# MCU.net
KiCad netlist of a schematic drawn in Altium Designer
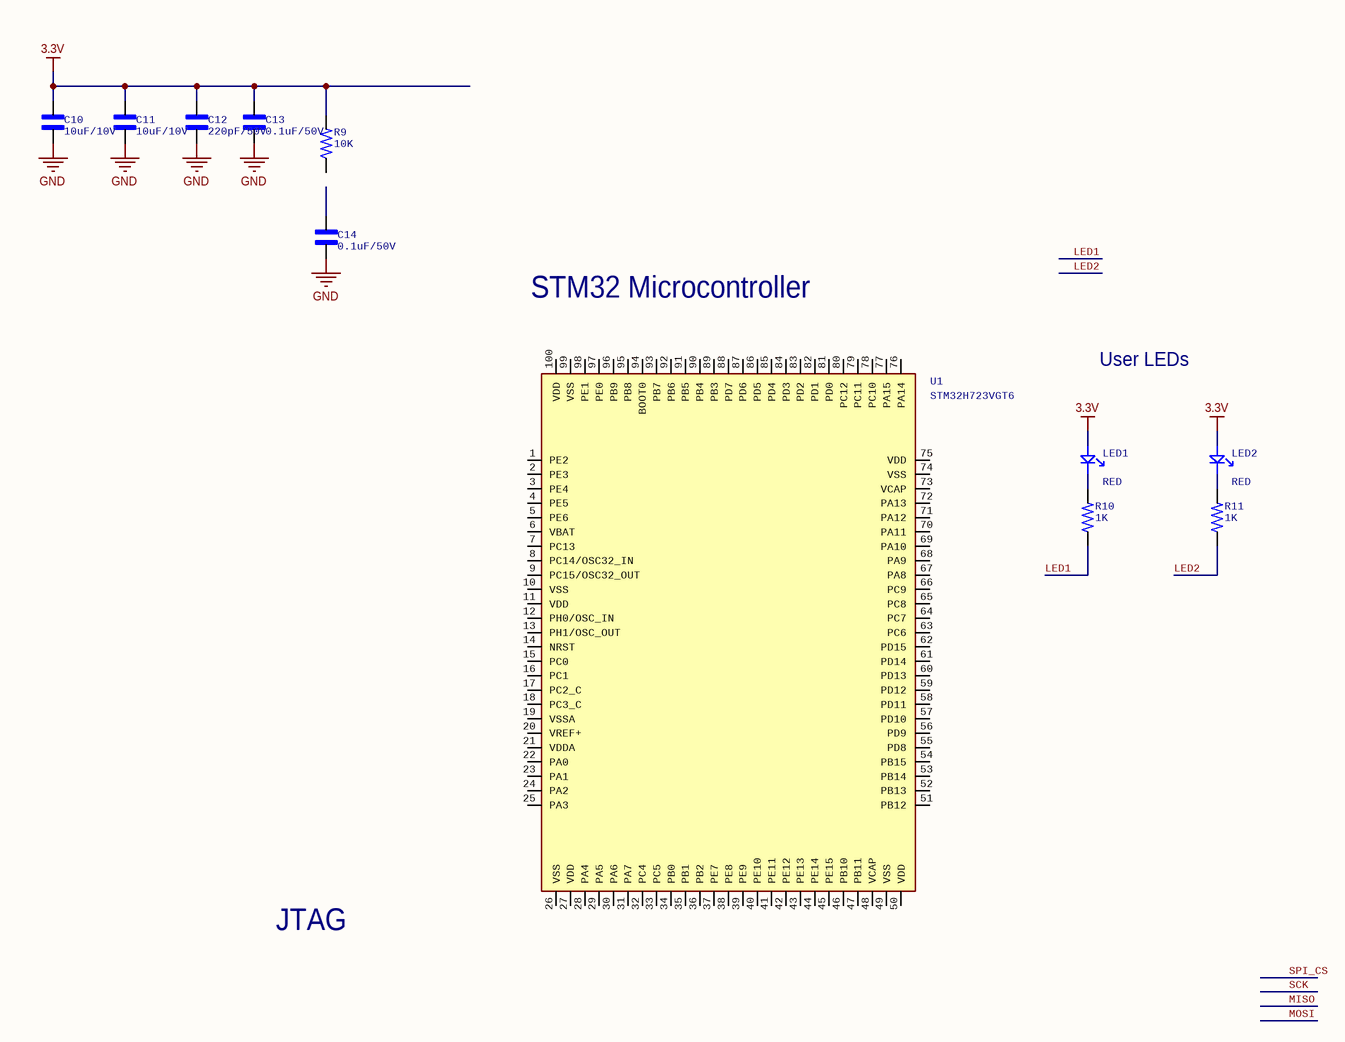
[diagram p0: MCU.SchDoc]

(export (version "E")
  (design (tool "Eeschema 10.0.6"))
  (components
    (comp (ref "C10")
      (value "10uF/10V")
      (footprint "C0603")
      (description "MLCC 10uF 10V X5R 20% 0603")
      (fields
        (field (name "MANUFACTURER") "KEMET")
        (field (name "MANUFACTURER PART NUMBER") "C0603C106M8PAC7867")
      )
      (libsource (lib "Capacitors") (part "C0603 10uF/10V"))
    )
    (comp (ref "C11")
      (value "10uF/10V")
      (footprint "C0603")
      (description "MLCC 10uF 10V X5R 20% 0603")
      (fields
        (field (name "MANUFACTURER") "KEMET")
        (field (name "MANUFACTURER PART NUMBER") "C0603C106M8PAC7867")
      )
      (libsource (lib "Capacitors") (part "C0603 10uF/10V"))
    )
    (comp (ref "C12")
      (value "220pF/50V")
      (footprint "C0603")
      (description "MLCC 220pF 50V X7R 10% 0603")
      (fields
        (field (name "MANUFACTURER") "KEMET")
        (field (name "MANUFACTURER PART NUMBER") "C0603C221K5RACTU")
      )
      (libsource (lib "Capacitors") (part "C0603 220pF/50V"))
    )
    (comp (ref "C13")
      (value "0.1uF/50V")
      (footprint "C0603")
      (description "MLCC 0.1uF 50V X5R 10% 0603")
      (fields
        (field (name "MANUFACTURER") "TDK")
        (field (name "MANUFACTURER PART NUMBER") "C1608X5R1H104K080AA")
      )
      (libsource (lib "Capacitors") (part "C0603 0.1uF/50V"))
    )
    (comp (ref "C14")
      (value "0.1uF/50V")
      (footprint "C0603")
      (description "MLCC 0.1uF 50V X5R 10% 0603")
      (fields
        (field (name "MANUFACTURER") "TDK")
        (field (name "MANUFACTURER PART NUMBER") "C1608X5R1H104K080AA")
      )
      (libsource (lib "Capacitors") (part "C0603 0.1uF/50V"))
    )
    (comp (ref "LED1")
      (value "RED")
      (footprint "LED 0603")
      (description "Red 625nm LED Indication - Discrete 2V 0603")
      (fields
        (field (name "MANUFACTURER") "Wurth Electronics")
        (field (name "MANUFACTURER PART NUMBER") "150060RS55040")
      )
      (libsource (lib "LED") (part "LED 0603 RED"))
    )
    (comp (ref "LED2")
      (value "RED")
      (footprint "LED 0603")
      (description "Red 625nm LED Indication - Discrete 2V 0603")
      (fields
        (field (name "MANUFACTURER") "Wurth Electronics")
        (field (name "MANUFACTURER PART NUMBER") "150060RS55040")
      )
      (libsource (lib "LED") (part "LED 0603 RED"))
    )
    (comp (ref "R9")
      (value "10K")
      (footprint "R0603")
      (description "RES 0603 10K OHM 1% 1/10W")
      (fields
        (field (name "MANUFACTURER") "Yageo")
        (field (name "MANUFACTURER PART NUMBER") "RC0603FR-0710KP")
      )
      (libsource (lib "Resistors") (part "R0603 10K"))
    )
    (comp (ref "R10")
      (value "1K")
      (footprint "R0603")
      (description "RES 0603 1K OHM 1% 1/10W")
      (fields
        (field (name "MANUFACTURER") "Yageo")
        (field (name "MANUFACTURER PART NUMBER") "RC0603FR-071KL")
      )
      (libsource (lib "Resistors") (part "R0603 1K"))
    )
    (comp (ref "R11")
      (value "1K")
      (footprint "R0603")
      (description "RES 0603 1K OHM 1% 1/10W")
      (fields
        (field (name "MANUFACTURER") "Yageo")
        (field (name "MANUFACTURER PART NUMBER") "RC0603FR-071KL")
      )
      (libsource (lib "Resistors") (part "R0603 1K"))
    )
    (comp (ref "U1")
      (value "STM32H723VGT6")
      (footprint "QFP-100")
      (description "MCU 32-bit ARM Cortex M7 RISC 1MB Flash 1.8V/2.5V/3.3V 100-Pin LQFP Tray")
      (fields (field (name "MANUFACTURER") "STMicroelectronics"))
      (libsource (lib "MCUs") (part "STM32H723VGT6"))
    )
  )
  (nets
    (net (code "1") (name "/LED1") (class "Default")
      (node (ref "R10") (pin "1") (pinfunction "1_1") (pintype "passive"))
    )
    (net (code "2") (name "/LED2") (class "Default")
      (node (ref "R11") (pin "1") (pinfunction "1_1") (pintype "passive"))
    )
    (net (code "7") (name "3.3V") (class "Default")
      (node (ref "C10") (pin "1") (pinfunction "1_1") (pintype "passive"))
      (node (ref "C11") (pin "1") (pinfunction "1_1") (pintype "passive"))
      (node (ref "C12") (pin "1") (pinfunction "1_1") (pintype "passive"))
      (node (ref "C13") (pin "1") (pinfunction "1_1") (pintype "passive"))
      (node (ref "LED1") (pin "1") (pinfunction "A_1") (pintype "passive"))
      (node (ref "LED2") (pin "1") (pinfunction "A_1") (pintype "passive"))
      (node (ref "R9") (pin "2") (pinfunction "2_2") (pintype "passive"))
    )
    (net (code "8") (name "GND") (class "Default")
      (node (ref "C10") (pin "2") (pinfunction "2_2") (pintype "passive"))
      (node (ref "C11") (pin "2") (pinfunction "2_2") (pintype "passive"))
      (node (ref "C12") (pin "2") (pinfunction "2_2") (pintype "passive"))
      (node (ref "C13") (pin "2") (pinfunction "2_2") (pintype "passive"))
      (node (ref "C14") (pin "2") (pinfunction "2_2") (pintype "passive"))
    )
    (net (code "9") (name "Net-(LED1-K)") (class "Default")
      (node (ref "LED1") (pin "2") (pinfunction "K_2") (pintype "passive"))
      (node (ref "R10") (pin "2") (pinfunction "2_2") (pintype "passive"))
    )
    (net (code "10") (name "Net-(LED2-K)") (class "Default")
      (node (ref "LED2") (pin "2") (pinfunction "K_2") (pintype "passive"))
      (node (ref "R11") (pin "2") (pinfunction "2_2") (pintype "passive"))
    )
    (net (code "11") (name "unconnected-(C14-Pad1)") (class "Default")
      (node (ref "C14") (pin "1") (pinfunction "1_1") (pintype "passive"))
    )
    (net (code "12") (name "unconnected-(R9-Pad1)") (class "Default")
      (node (ref "R9") (pin "1") (pinfunction "1_1") (pintype "passive"))
    )
    (net (code "13") (name "unconnected-(U1-BOOT0-Pad94)") (class "Default")
      (node (ref "U1") (pin "94") (pinfunction "BOOT0_94") (pintype "passive"))
    )
    (net (code "14") (name "unconnected-(U1-NRST-Pad14)") (class "Default")
      (node (ref "U1") (pin "14") (pinfunction "NRST_14") (pintype "passive"))
    )
    (net (code "15") (name "unconnected-(U1-PA0-Pad22)") (class "Default")
      (node (ref "U1") (pin "22") (pinfunction "PA0_22") (pintype "passive"))
    )
    (net (code "16") (name "unconnected-(U1-PA1-Pad23)") (class "Default")
      (node (ref "U1") (pin "23") (pinfunction "PA1_23") (pintype "passive"))
    )
    (net (code "17") (name "unconnected-(U1-PA2-Pad24)") (class "Default")
      (node (ref "U1") (pin "24") (pinfunction "PA2_24") (pintype "passive"))
    )
    (net (code "18") (name "unconnected-(U1-PA3-Pad25)") (class "Default")
      (node (ref "U1") (pin "25") (pinfunction "PA3_25") (pintype "passive"))
    )
    (net (code "19") (name "unconnected-(U1-PA4-Pad28)") (class "Default")
      (node (ref "U1") (pin "28") (pinfunction "PA4_28") (pintype "passive"))
    )
    (net (code "20") (name "unconnected-(U1-PA5-Pad29)") (class "Default")
      (node (ref "U1") (pin "29") (pinfunction "PA5_29") (pintype "passive"))
    )
    (net (code "21") (name "unconnected-(U1-PA6-Pad30)") (class "Default")
      (node (ref "U1") (pin "30") (pinfunction "PA6_30") (pintype "passive"))
    )
    (net (code "22") (name "unconnected-(U1-PA7-Pad31)") (class "Default")
      (node (ref "U1") (pin "31") (pinfunction "PA7_31") (pintype "passive"))
    )
    (net (code "23") (name "unconnected-(U1-PA8-Pad67)") (class "Default")
      (node (ref "U1") (pin "67") (pinfunction "PA8_67") (pintype "passive"))
    )
    (net (code "24") (name "unconnected-(U1-PA9-Pad68)") (class "Default")
      (node (ref "U1") (pin "68") (pinfunction "PA9_68") (pintype "passive"))
    )
    (net (code "25") (name "unconnected-(U1-PA10-Pad69)") (class "Default")
      (node (ref "U1") (pin "69") (pinfunction "PA10_69") (pintype "passive"))
    )
    (net (code "26") (name "unconnected-(U1-PA11-Pad70)") (class "Default")
      (node (ref "U1") (pin "70") (pinfunction "PA11_70") (pintype "passive"))
    )
    (net (code "27") (name "unconnected-(U1-PA12-Pad71)") (class "Default")
      (node (ref "U1") (pin "71") (pinfunction "PA12_71") (pintype "passive"))
    )
    (net (code "28") (name "unconnected-(U1-PA13-Pad72)") (class "Default")
      (node (ref "U1") (pin "72") (pinfunction "PA13_72") (pintype "passive"))
    )
    (net (code "29") (name "unconnected-(U1-PA14-Pad76)") (class "Default")
      (node (ref "U1") (pin "76") (pinfunction "PA14_76") (pintype "passive"))
    )
    (net (code "30") (name "unconnected-(U1-PA15-Pad77)") (class "Default")
      (node (ref "U1") (pin "77") (pinfunction "PA15_77") (pintype "passive"))
    )
    (net (code "31") (name "unconnected-(U1-PB0-Pad34)") (class "Default")
      (node (ref "U1") (pin "34") (pinfunction "PB0_34") (pintype "passive"))
    )
    (net (code "32") (name "unconnected-(U1-PB1-Pad35)") (class "Default")
      (node (ref "U1") (pin "35") (pinfunction "PB1_35") (pintype "passive"))
    )
    (net (code "33") (name "unconnected-(U1-PB2-Pad36)") (class "Default")
      (node (ref "U1") (pin "36") (pinfunction "PB2_36") (pintype "passive"))
    )
    (net (code "34") (name "unconnected-(U1-PB3-Pad89)") (class "Default")
      (node (ref "U1") (pin "89") (pinfunction "PB3_89") (pintype "passive"))
    )
    (net (code "35") (name "unconnected-(U1-PB4-Pad90)") (class "Default")
      (node (ref "U1") (pin "90") (pinfunction "PB4_90") (pintype "passive"))
    )
    (net (code "36") (name "unconnected-(U1-PB5-Pad91)") (class "Default")
      (node (ref "U1") (pin "91") (pinfunction "PB5_91") (pintype "passive"))
    )
    (net (code "37") (name "unconnected-(U1-PB6-Pad92)") (class "Default")
      (node (ref "U1") (pin "92") (pinfunction "PB6_92") (pintype "passive"))
    )
    (net (code "38") (name "unconnected-(U1-PB7-Pad93)") (class "Default")
      (node (ref "U1") (pin "93") (pinfunction "PB7_93") (pintype "passive"))
    )
    (net (code "39") (name "unconnected-(U1-PB8-Pad95)") (class "Default")
      (node (ref "U1") (pin "95") (pinfunction "PB8_95") (pintype "passive"))
    )
    (net (code "40") (name "unconnected-(U1-PB9-Pad96)") (class "Default")
      (node (ref "U1") (pin "96") (pinfunction "PB9_96") (pintype "passive"))
    )
    (net (code "41") (name "unconnected-(U1-PB10-Pad46)") (class "Default")
      (node (ref "U1") (pin "46") (pinfunction "PB10_46") (pintype "passive"))
    )
    (net (code "42") (name "unconnected-(U1-PB11-Pad47)") (class "Default")
      (node (ref "U1") (pin "47") (pinfunction "PB11_47") (pintype "passive"))
    )
    (net (code "43") (name "unconnected-(U1-PB12-Pad51)") (class "Default")
      (node (ref "U1") (pin "51") (pinfunction "PB12_51") (pintype "passive"))
    )
    (net (code "44") (name "unconnected-(U1-PB13-Pad52)") (class "Default")
      (node (ref "U1") (pin "52") (pinfunction "PB13_52") (pintype "passive"))
    )
    (net (code "45") (name "unconnected-(U1-PB14-Pad53)") (class "Default")
      (node (ref "U1") (pin "53") (pinfunction "PB14_53") (pintype "passive"))
    )
    (net (code "46") (name "unconnected-(U1-PB15-Pad54)") (class "Default")
      (node (ref "U1") (pin "54") (pinfunction "PB15_54") (pintype "passive"))
    )
    (net (code "47") (name "unconnected-(U1-PC0-Pad15)") (class "Default")
      (node (ref "U1") (pin "15") (pinfunction "PC0_15") (pintype "passive"))
    )
    (net (code "48") (name "unconnected-(U1-PC1-Pad16)") (class "Default")
      (node (ref "U1") (pin "16") (pinfunction "PC1_16") (pintype "passive"))
    )
    (net (code "49") (name "unconnected-(U1-PC2_C-Pad17)") (class "Default")
      (node (ref "U1") (pin "17") (pinfunction "PC2_C_17") (pintype "passive"))
    )
    (net (code "50") (name "unconnected-(U1-PC3_C-Pad18)") (class "Default")
      (node (ref "U1") (pin "18") (pinfunction "PC3_C_18") (pintype "passive"))
    )
    (net (code "51") (name "unconnected-(U1-PC4-Pad32)") (class "Default")
      (node (ref "U1") (pin "32") (pinfunction "PC4_32") (pintype "passive"))
    )
    (net (code "52") (name "unconnected-(U1-PC5-Pad33)") (class "Default")
      (node (ref "U1") (pin "33") (pinfunction "PC5_33") (pintype "passive"))
    )
    (net (code "53") (name "unconnected-(U1-PC6-Pad63)") (class "Default")
      (node (ref "U1") (pin "63") (pinfunction "PC6_63") (pintype "passive"))
    )
    (net (code "54") (name "unconnected-(U1-PC7-Pad64)") (class "Default")
      (node (ref "U1") (pin "64") (pinfunction "PC7_64") (pintype "passive"))
    )
    (net (code "55") (name "unconnected-(U1-PC8-Pad65)") (class "Default")
      (node (ref "U1") (pin "65") (pinfunction "PC8_65") (pintype "passive"))
    )
    (net (code "56") (name "unconnected-(U1-PC9-Pad66)") (class "Default")
      (node (ref "U1") (pin "66") (pinfunction "PC9_66") (pintype "passive"))
    )
    (net (code "57") (name "unconnected-(U1-PC10-Pad78)") (class "Default")
      (node (ref "U1") (pin "78") (pinfunction "PC10_78") (pintype "passive"))
    )
    (net (code "58") (name "unconnected-(U1-PC11-Pad79)") (class "Default")
      (node (ref "U1") (pin "79") (pinfunction "PC11_79") (pintype "passive"))
    )
    (net (code "59") (name "unconnected-(U1-PC12-Pad80)") (class "Default")
      (node (ref "U1") (pin "80") (pinfunction "PC12_80") (pintype "passive"))
    )
    (net (code "60") (name "unconnected-(U1-PC13-Pad7)") (class "Default")
      (node (ref "U1") (pin "7") (pinfunction "PC13_7") (pintype "passive"))
    )
    (net (code "61") (name "unconnected-(U1-PC14{slash}OSC32_IN-Pad8)") (class "Default")
      (node (ref "U1") (pin "8") (pinfunction "PC14/OSC32_IN_8") (pintype "passive"))
    )
    (net (code "62") (name "unconnected-(U1-PC15{slash}OSC32_OUT-Pad9)") (class "Default")
      (node (ref "U1") (pin "9") (pinfunction "PC15/OSC32_OUT_9") (pintype "passive"))
    )
    (net (code "63") (name "unconnected-(U1-PD0-Pad81)") (class "Default")
      (node (ref "U1") (pin "81") (pinfunction "PD0_81") (pintype "passive"))
    )
    (net (code "64") (name "unconnected-(U1-PD1-Pad82)") (class "Default")
      (node (ref "U1") (pin "82") (pinfunction "PD1_82") (pintype "passive"))
    )
    (net (code "65") (name "unconnected-(U1-PD2-Pad83)") (class "Default")
      (node (ref "U1") (pin "83") (pinfunction "PD2_83") (pintype "passive"))
    )
    (net (code "66") (name "unconnected-(U1-PD3-Pad84)") (class "Default")
      (node (ref "U1") (pin "84") (pinfunction "PD3_84") (pintype "passive"))
    )
    (net (code "67") (name "unconnected-(U1-PD4-Pad85)") (class "Default")
      (node (ref "U1") (pin "85") (pinfunction "PD4_85") (pintype "passive"))
    )
    (net (code "68") (name "unconnected-(U1-PD5-Pad86)") (class "Default")
      (node (ref "U1") (pin "86") (pinfunction "PD5_86") (pintype "passive"))
    )
    (net (code "69") (name "unconnected-(U1-PD6-Pad87)") (class "Default")
      (node (ref "U1") (pin "87") (pinfunction "PD6_87") (pintype "passive"))
    )
    (net (code "70") (name "unconnected-(U1-PD7-Pad88)") (class "Default")
      (node (ref "U1") (pin "88") (pinfunction "PD7_88") (pintype "passive"))
    )
    (net (code "71") (name "unconnected-(U1-PD8-Pad55)") (class "Default")
      (node (ref "U1") (pin "55") (pinfunction "PD8_55") (pintype "passive"))
    )
    (net (code "72") (name "unconnected-(U1-PD9-Pad56)") (class "Default")
      (node (ref "U1") (pin "56") (pinfunction "PD9_56") (pintype "passive"))
    )
    (net (code "73") (name "unconnected-(U1-PD10-Pad57)") (class "Default")
      (node (ref "U1") (pin "57") (pinfunction "PD10_57") (pintype "passive"))
    )
    (net (code "74") (name "unconnected-(U1-PD11-Pad58)") (class "Default")
      (node (ref "U1") (pin "58") (pinfunction "PD11_58") (pintype "passive"))
    )
    (net (code "75") (name "unconnected-(U1-PD12-Pad59)") (class "Default")
      (node (ref "U1") (pin "59") (pinfunction "PD12_59") (pintype "passive"))
    )
    (net (code "76") (name "unconnected-(U1-PD13-Pad60)") (class "Default")
      (node (ref "U1") (pin "60") (pinfunction "PD13_60") (pintype "passive"))
    )
    (net (code "77") (name "unconnected-(U1-PD14-Pad61)") (class "Default")
      (node (ref "U1") (pin "61") (pinfunction "PD14_61") (pintype "passive"))
    )
    (net (code "78") (name "unconnected-(U1-PD15-Pad62)") (class "Default")
      (node (ref "U1") (pin "62") (pinfunction "PD15_62") (pintype "passive"))
    )
    (net (code "79") (name "unconnected-(U1-PE0-Pad97)") (class "Default")
      (node (ref "U1") (pin "97") (pinfunction "PE0_97") (pintype "passive"))
    )
    (net (code "80") (name "unconnected-(U1-PE1-Pad98)") (class "Default")
      (node (ref "U1") (pin "98") (pinfunction "PE1_98") (pintype "passive"))
    )
    (net (code "81") (name "unconnected-(U1-PE2-Pad1)") (class "Default")
      (node (ref "U1") (pin "1") (pinfunction "PE2_1") (pintype "passive"))
    )
    (net (code "82") (name "unconnected-(U1-PE3-Pad2)") (class "Default")
      (node (ref "U1") (pin "2") (pinfunction "PE3_2") (pintype "passive"))
    )
    (net (code "83") (name "unconnected-(U1-PE4-Pad3)") (class "Default")
      (node (ref "U1") (pin "3") (pinfunction "PE4_3") (pintype "passive"))
    )
    (net (code "84") (name "unconnected-(U1-PE5-Pad4)") (class "Default")
      (node (ref "U1") (pin "4") (pinfunction "PE5_4") (pintype "passive"))
    )
    (net (code "85") (name "unconnected-(U1-PE6-Pad5)") (class "Default")
      (node (ref "U1") (pin "5") (pinfunction "PE6_5") (pintype "passive"))
    )
    (net (code "86") (name "unconnected-(U1-PE7-Pad37)") (class "Default")
      (node (ref "U1") (pin "37") (pinfunction "PE7_37") (pintype "passive"))
    )
    (net (code "87") (name "unconnected-(U1-PE8-Pad38)") (class "Default")
      (node (ref "U1") (pin "38") (pinfunction "PE8_38") (pintype "passive"))
    )
    (net (code "88") (name "unconnected-(U1-PE9-Pad39)") (class "Default")
      (node (ref "U1") (pin "39") (pinfunction "PE9_39") (pintype "passive"))
    )
    (net (code "89") (name "unconnected-(U1-PE10-Pad40)") (class "Default")
      (node (ref "U1") (pin "40") (pinfunction "PE10_40") (pintype "passive"))
    )
    (net (code "90") (name "unconnected-(U1-PE11-Pad41)") (class "Default")
      (node (ref "U1") (pin "41") (pinfunction "PE11_41") (pintype "passive"))
    )
    (net (code "91") (name "unconnected-(U1-PE12-Pad42)") (class "Default")
      (node (ref "U1") (pin "42") (pinfunction "PE12_42") (pintype "passive"))
    )
    (net (code "92") (name "unconnected-(U1-PE13-Pad43)") (class "Default")
      (node (ref "U1") (pin "43") (pinfunction "PE13_43") (pintype "passive"))
    )
    (net (code "93") (name "unconnected-(U1-PE14-Pad44)") (class "Default")
      (node (ref "U1") (pin "44") (pinfunction "PE14_44") (pintype "passive"))
    )
    (net (code "94") (name "unconnected-(U1-PE15-Pad45)") (class "Default")
      (node (ref "U1") (pin "45") (pinfunction "PE15_45") (pintype "passive"))
    )
    (net (code "95") (name "unconnected-(U1-PH0{slash}OSC_IN-Pad12)") (class "Default")
      (node (ref "U1") (pin "12") (pinfunction "PH0/OSC_IN_12") (pintype "passive"))
    )
    (net (code "96") (name "unconnected-(U1-PH1{slash}OSC_OUT-Pad13)") (class "Default")
      (node (ref "U1") (pin "13") (pinfunction "PH1/OSC_OUT_13") (pintype "passive"))
    )
    (net (code "97") (name "unconnected-(U1-VBAT-Pad6)") (class "Default")
      (node (ref "U1") (pin "6") (pinfunction "VBAT_6") (pintype "passive"))
    )
    (net (code "98") (name "unconnected-(U1-VCAP-Pad48)") (class "Default")
      (node (ref "U1") (pin "48") (pinfunction "VCAP_48") (pintype "passive"))
    )
    (net (code "99") (name "unconnected-(U1-VCAP-Pad73)") (class "Default")
      (node (ref "U1") (pin "73") (pinfunction "VCAP_73") (pintype "passive"))
    )
    (net (code "100") (name "unconnected-(U1-VDD-Pad11)") (class "Default")
      (node (ref "U1") (pin "11") (pinfunction "VDD_11") (pintype "passive"))
    )
    (net (code "101") (name "unconnected-(U1-VDD-Pad27)") (class "Default")
      (node (ref "U1") (pin "27") (pinfunction "VDD_27") (pintype "passive"))
    )
    (net (code "102") (name "unconnected-(U1-VDD-Pad50)") (class "Default")
      (node (ref "U1") (pin "50") (pinfunction "VDD_50") (pintype "passive"))
    )
    (net (code "103") (name "unconnected-(U1-VDD-Pad75)") (class "Default")
      (node (ref "U1") (pin "75") (pinfunction "VDD_75") (pintype "passive"))
    )
    (net (code "104") (name "unconnected-(U1-VDD-Pad100)") (class "Default")
      (node (ref "U1") (pin "100") (pinfunction "VDD_100") (pintype "passive"))
    )
    (net (code "105") (name "unconnected-(U1-VDDA-Pad21)") (class "Default")
      (node (ref "U1") (pin "21") (pinfunction "VDDA_21") (pintype "passive"))
    )
    (net (code "106") (name "unconnected-(U1-VREF+-Pad20)") (class "Default")
      (node (ref "U1") (pin "20") (pinfunction "VREF+_20") (pintype "passive"))
    )
    (net (code "107") (name "unconnected-(U1-VSS-Pad10)") (class "Default")
      (node (ref "U1") (pin "10") (pinfunction "VSS_10") (pintype "passive"))
    )
    (net (code "108") (name "unconnected-(U1-VSS-Pad26)") (class "Default")
      (node (ref "U1") (pin "26") (pinfunction "VSS_26") (pintype "passive"))
    )
    (net (code "109") (name "unconnected-(U1-VSS-Pad49)") (class "Default")
      (node (ref "U1") (pin "49") (pinfunction "VSS_49") (pintype "passive"))
    )
    (net (code "110") (name "unconnected-(U1-VSS-Pad74)") (class "Default")
      (node (ref "U1") (pin "74") (pinfunction "VSS_74") (pintype "passive"))
    )
    (net (code "111") (name "unconnected-(U1-VSS-Pad99)") (class "Default")
      (node (ref "U1") (pin "99") (pinfunction "VSS_99") (pintype "passive"))
    )
    (net (code "112") (name "unconnected-(U1-VSSA-Pad19)") (class "Default")
      (node (ref "U1") (pin "19") (pinfunction "VSSA_19") (pintype "passive"))
    )
  )
)
